# IO.net
KiCad netlist of a schematic drawn in Altium Designer
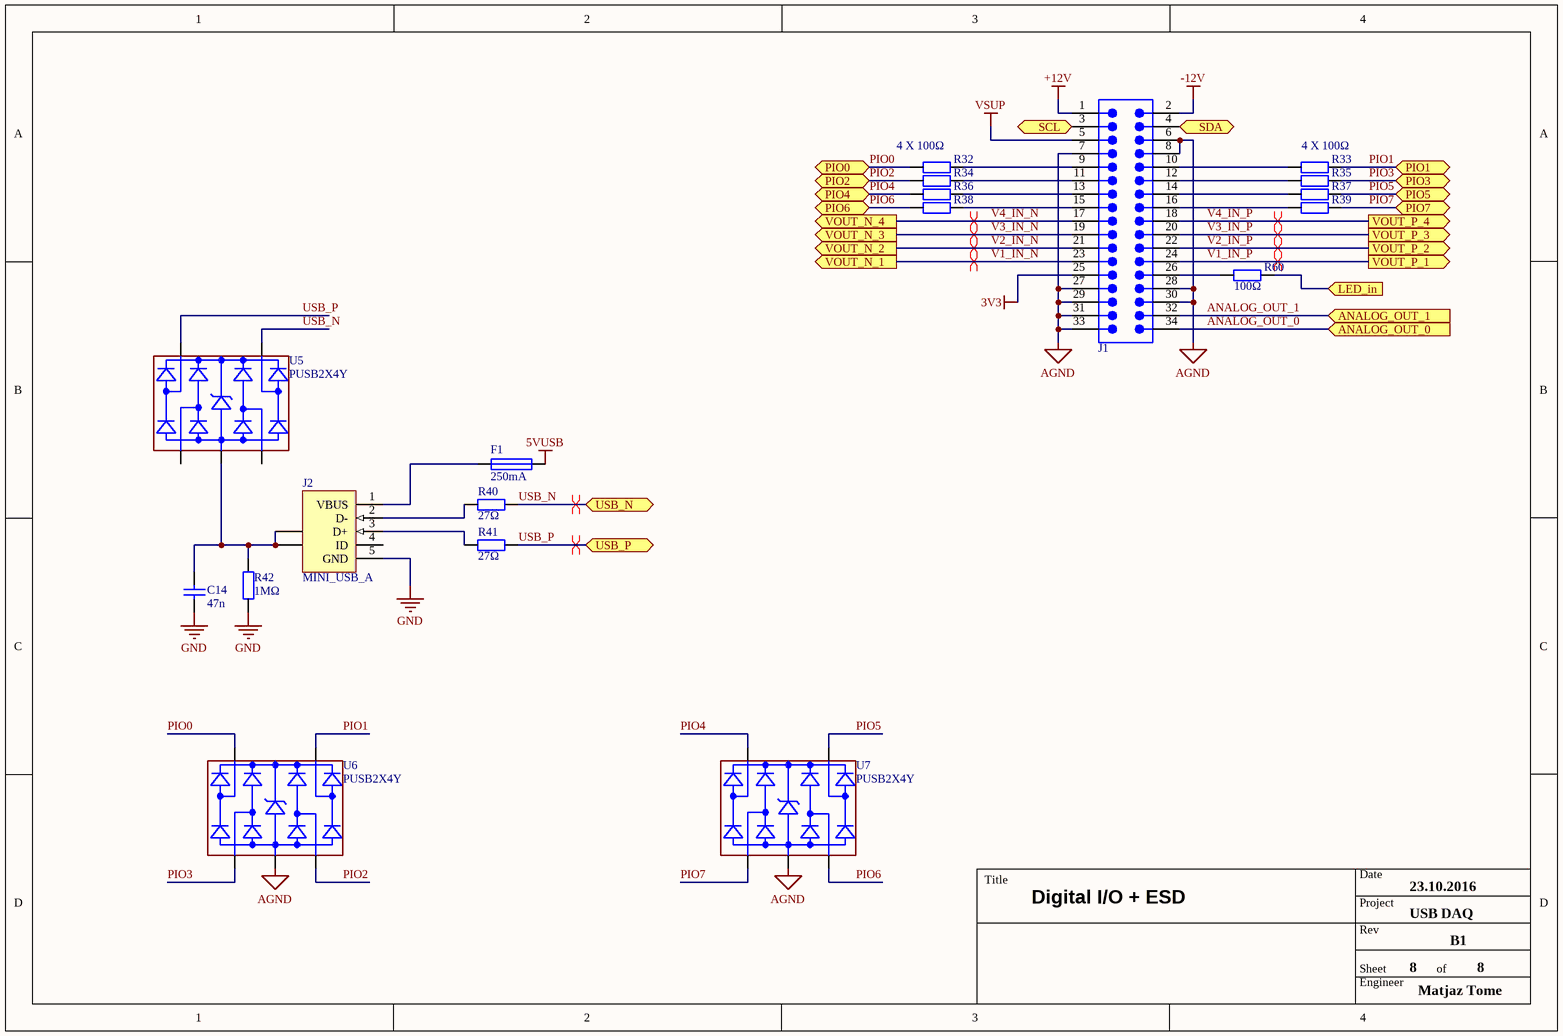
[diagram p0: IO.SchDoc]

(export (version "E")
  (design (tool "Eeschema 10.0.6"))
  (components
    (comp (ref "C14")
      (value "47n")
      (footprint "0603C")
      (description "ceramic X7R SMD capacitor smd 0603 47nF 16V")
      (fields (field (name "PART NUMBER") "RSC0007") (field (name "MANUFACTURER") "Multicomp"))
      (libsource (lib "components") (part "Capacitor"))
    )
    (comp (ref "F1")
      (value "250mA")
      (footprint "1206")
      (description "Polyfuse 250 mA holding current, 500 mA trip current")
      (fields (field (name "PART NUMBER") "XXF0001") (field (name "MANUFACTURER") "Littelfuse"))
      (libsource (lib "components") (part "Fuse"))
    )
    (comp (ref "J1")
      (value "IDC34R")
      (footprint "IDC34R")
      (description "Harting IDC connector 2X17")
      (fields (field (name "PART NUMBER") "CHI0002") (field (name "MANUFACTURER") "Harting"))
      (libsource (lib "components") (part "IDC34R"))
    )
    (comp (ref "J2")
      (value "MINI_USB_A")
      (footprint "MICRO_USB_A")
      (description "CONNECTOR, MICRO USB B, SMD, 5WAY")
      (fields (field (name "PART NUMBER") "XCU0003") (field (name "MANUFACTURER") "FCI"))
      (libsource (lib "components") (part "MINI_USB_A"))
    )
    (comp (ref "R32")
      (value "100Ω")
      (footprint "0603R")
      (description "resistor smd 0603 100Ω 5% 0.1w")
      (fields (field (name "PART NUMBER") "XRS0016") (field (name "MANUFACTURER") "Multicomp"))
      (libsource (lib "components") (part "Resistor"))
    )
    (comp (ref "R33")
      (value "100Ω")
      (footprint "0603R")
      (description "resistor smd 0603 100Ω 5% 0.1w")
      (fields (field (name "PART NUMBER") "XRS0016") (field (name "MANUFACTURER") "Multicomp"))
      (libsource (lib "components") (part "Resistor"))
    )
    (comp (ref "R34")
      (value "100Ω")
      (footprint "0603R")
      (description "resistor smd 0603 100Ω 5% 0.1w")
      (fields (field (name "PART NUMBER") "XRS0016") (field (name "MANUFACTURER") "Multicomp"))
      (libsource (lib "components") (part "Resistor"))
    )
    (comp (ref "R35")
      (value "100Ω")
      (footprint "0603R")
      (description "resistor smd 0603 100Ω 5% 0.1w")
      (fields (field (name "PART NUMBER") "XRS0016") (field (name "MANUFACTURER") "Multicomp"))
      (libsource (lib "components") (part "Resistor"))
    )
    (comp (ref "R36")
      (value "100Ω")
      (footprint "0603R")
      (description "resistor smd 0603 100Ω 5% 0.1w")
      (fields (field (name "PART NUMBER") "XRS0016") (field (name "MANUFACTURER") "Multicomp"))
      (libsource (lib "components") (part "Resistor"))
    )
    (comp (ref "R37")
      (value "100Ω")
      (footprint "0603R")
      (description "resistor smd 0603 100Ω 5% 0.1w")
      (fields (field (name "PART NUMBER") "XRS0016") (field (name "MANUFACTURER") "Multicomp"))
      (libsource (lib "components") (part "Resistor"))
    )
    (comp (ref "R38")
      (value "100Ω")
      (footprint "0603R")
      (description "resistor smd 0603 100Ω 5% 0.1w")
      (fields (field (name "PART NUMBER") "XRS0016") (field (name "MANUFACTURER") "Multicomp"))
      (libsource (lib "components") (part "Resistor"))
    )
    (comp (ref "R39")
      (value "100Ω")
      (footprint "0603R")
      (description "resistor smd 0603 100Ω 5% 0.1w")
      (fields (field (name "PART NUMBER") "XRS0016") (field (name "MANUFACTURER") "Multicomp"))
      (libsource (lib "components") (part "Resistor"))
    )
    (comp (ref "R40")
      (value "27Ω")
      (footprint "0603R")
      (description "resistor smd 0603 27Ω 5% 0.1w")
      (fields (field (name "PART NUMBER") "XRS0033") (field (name "MANUFACTURER") "Panasonic"))
      (libsource (lib "components") (part "Resistor"))
    )
    (comp (ref "R41")
      (value "27Ω")
      (footprint "0603R")
      (description "resistor smd 0603 27Ω 5% 0.1w")
      (fields (field (name "PART NUMBER") "XRS0033") (field (name "MANUFACTURER") "Panasonic"))
      (libsource (lib "components") (part "Resistor"))
    )
    (comp (ref "R42")
      (value "1MΩ")
      (footprint "0603R")
      (description "resistor smd 0603 1MΩ 5% 0.1w")
      (fields (field (name "PART NUMBER") "XRS0035") (field (name "MANUFACTURER") "Multicomp"))
      (libsource (lib "") (part "Resistor_1"))
    )
    (comp (ref "R60")
      (value "100Ω")
      (footprint "0603R")
      (description "resistor smd 0603 100Ω 5% 0.1w")
      (fields (field (name "PART NUMBER") "XRS0016") (field (name "MANUFACTURER") "Multicomp"))
      (libsource (lib "components") (part "Resistor"))
    )
    (comp (ref "U5")
      (value "PUSB2X4Y")
      (footprint "SOT363")
      (description "ESD protection for high-speed interfaces")
      (fields (field (name "PART NUMBER") "XDE0000") (field (name "MANUFACTURER") "Multicomp"))
      (libsource (lib "components") (part "ESD2_4CH"))
    )
    (comp (ref "U6")
      (value "PUSB2X4Y")
      (footprint "SOT363")
      (description "ESD protection for high-speed interfaces")
      (fields (field (name "PART NUMBER") "XDE0000") (field (name "MANUFACTURER") "Multicomp"))
      (libsource (lib "components") (part "ESD2_4CH"))
    )
    (comp (ref "U7")
      (value "PUSB2X4Y")
      (footprint "SOT363")
      (description "ESD protection for high-speed interfaces")
      (fields (field (name "PART NUMBER") "XDE0000") (field (name "MANUFACTURER") "Multicomp"))
      (libsource (lib "components") (part "ESD2_4CH"))
    )
  )
  (nets
    (net (code "1") (name "+12V") (class "Default")
      (node (ref "J1") (pin "1") (pinfunction "1_1") (pintype "passive"))
    )
    (net (code "2") (name "-12V") (class "Default")
      (node (ref "J1") (pin "2") (pinfunction "2_2") (pintype "passive"))
    )
    (net (code "3") (name "/ANALOG_OUT_0") (class "Default")
      (node (ref "J1") (pin "34") (pinfunction "34_34") (pintype "passive"))
    )
    (net (code "4") (name "/ANALOG_OUT_1") (class "Default")
      (node (ref "J1") (pin "32") (pinfunction "32_32") (pintype "passive"))
    )
    (net (code "5") (name "/LED_in") (class "Default")
      (node (ref "R60") (pin "2") (pinfunction "2_2") (pintype "passive"))
    )
    (net (code "6") (name "/PIO0") (class "Default")
      (node (ref "R32") (pin "1") (pinfunction "1_1") (pintype "passive"))
      (node (ref "U6") (pin "6") (pinfunction "6_6") (pintype "passive"))
    )
    (net (code "7") (name "/PIO1") (class "Default")
      (node (ref "R33") (pin "2") (pinfunction "2_2") (pintype "passive"))
      (node (ref "U6") (pin "4") (pinfunction "4_4") (pintype "passive"))
    )
    (net (code "8") (name "/PIO2") (class "Default")
      (node (ref "R34") (pin "1") (pinfunction "1_1") (pintype "passive"))
      (node (ref "U6") (pin "3") (pinfunction "3_3") (pintype "passive"))
    )
    (net (code "9") (name "/PIO3") (class "Default")
      (node (ref "R35") (pin "2") (pinfunction "2_2") (pintype "passive"))
      (node (ref "U6") (pin "1") (pinfunction "1_1") (pintype "passive"))
    )
    (net (code "10") (name "/PIO4") (class "Default")
      (node (ref "R36") (pin "1") (pinfunction "1_1") (pintype "passive"))
      (node (ref "U7") (pin "6") (pinfunction "6_6") (pintype "passive"))
    )
    (net (code "11") (name "/PIO5") (class "Default")
      (node (ref "R37") (pin "2") (pinfunction "2_2") (pintype "passive"))
      (node (ref "U7") (pin "4") (pinfunction "4_4") (pintype "passive"))
    )
    (net (code "12") (name "/PIO6") (class "Default")
      (node (ref "R38") (pin "1") (pinfunction "1_1") (pintype "passive"))
      (node (ref "U7") (pin "3") (pinfunction "3_3") (pintype "passive"))
    )
    (net (code "13") (name "/PIO7") (class "Default")
      (node (ref "R39") (pin "2") (pinfunction "2_2") (pintype "passive"))
      (node (ref "U7") (pin "1") (pinfunction "1_1") (pintype "passive"))
    )
    (net (code "14") (name "/SCL") (class "Default")
      (node (ref "J1") (pin "3") (pinfunction "3_3") (pintype "passive"))
    )
    (net (code "15") (name "/SDA") (class "Default")
      (node (ref "J1") (pin "4") (pinfunction "4_4") (pintype "passive"))
    )
    (net (code "16") (name "/USB_N") (class "Default")
      (node (ref "R40") (pin "2") (pinfunction "2_2") (pintype "passive"))
      (node (ref "U5") (pin "4") (pinfunction "4_4") (pintype "passive"))
    )
    (net (code "17") (name "/USB_P") (class "Default")
      (node (ref "R41") (pin "2") (pinfunction "2_2") (pintype "passive"))
      (node (ref "U5") (pin "6") (pinfunction "6_6") (pintype "passive"))
    )
    (net (code "18") (name "/V1_IN_N") (class "Default")
      (node (ref "J1") (pin "23") (pinfunction "23_23") (pintype "passive"))
    )
    (net (code "19") (name "/V1_IN_P") (class "Default")
      (node (ref "J1") (pin "24") (pinfunction "24_24") (pintype "passive"))
    )
    (net (code "20") (name "/V2_IN_N") (class "Default")
      (node (ref "J1") (pin "21") (pinfunction "21_21") (pintype "passive"))
    )
    (net (code "21") (name "/V2_IN_P") (class "Default")
      (node (ref "J1") (pin "22") (pinfunction "22_22") (pintype "passive"))
    )
    (net (code "22") (name "/V3_IN_N") (class "Default")
      (node (ref "J1") (pin "19") (pinfunction "19_19") (pintype "passive"))
    )
    (net (code "23") (name "/V3_IN_P") (class "Default")
      (node (ref "J1") (pin "20") (pinfunction "20_20") (pintype "passive"))
    )
    (net (code "24") (name "/V4_IN_N") (class "Default")
      (node (ref "J1") (pin "17") (pinfunction "17_17") (pintype "passive"))
    )
    (net (code "25") (name "/V4_IN_P") (class "Default")
      (node (ref "J1") (pin "18") (pinfunction "18_18") (pintype "passive"))
    )
    (net (code "26") (name "3V3") (class "Default")
      (node (ref "J1") (pin "25") (pinfunction "25_25") (pintype "passive"))
    )
    (net (code "27") (name "5VUSB") (class "Default")
      (node (ref "F1") (pin "2") (pinfunction "2_2") (pintype "passive"))
    )
    (net (code "28") (name "AGND") (class "Default")
      (node (ref "J1") (pin "27") (pinfunction "27_27") (pintype "passive"))
      (node (ref "J1") (pin "28") (pinfunction "28_28") (pintype "passive"))
      (node (ref "J1") (pin "29") (pinfunction "29_29") (pintype "passive"))
      (node (ref "J1") (pin "30") (pinfunction "30_30") (pintype "passive"))
      (node (ref "J1") (pin "31") (pinfunction "31_31") (pintype "passive"))
      (node (ref "J1") (pin "33") (pinfunction "33_33") (pintype "passive"))
      (node (ref "J1") (pin "6") (pinfunction "6_6") (pintype "passive"))
      (node (ref "J1") (pin "7") (pinfunction "7_7") (pintype "passive"))
      (node (ref "J1") (pin "8") (pinfunction "8_8") (pintype "passive"))
      (node (ref "U6") (pin "2") (pinfunction "2_2") (pintype "passive"))
      (node (ref "U7") (pin "2") (pinfunction "2_2") (pintype "passive"))
    )
    (net (code "29") (name "GND") (class "Default")
      (node (ref "C14") (pin "1") (pinfunction "1_1") (pintype "passive"))
      (node (ref "J2") (pin "5") (pinfunction "GND_5") (pintype "power_in"))
      (node (ref "R42") (pin "1") (pinfunction "1_1") (pintype "passive"))
    )
    (net (code "30") (name "Net-(C14-Pad2)") (class "Default")
      (node (ref "C14") (pin "2") (pinfunction "2_2") (pintype "passive"))
      (node (ref "J2") (pin "6") (pinfunction "SHLD_6") (pintype "passive"))
      (node (ref "J2") (pin "7") (pinfunction "SHLD_7") (pintype "passive"))
      (node (ref "R42") (pin "2") (pinfunction "2_2") (pintype "passive"))
      (node (ref "U5") (pin "2") (pinfunction "2_2") (pintype "passive"))
    )
    (net (code "31") (name "Net-(J1-Pad9)") (class "Default")
      (node (ref "J1") (pin "9") (pinfunction "9_9") (pintype "passive"))
      (node (ref "R32") (pin "2") (pinfunction "2_2") (pintype "passive"))
    )
    (net (code "32") (name "Net-(J1-Pad10)") (class "Default")
      (node (ref "J1") (pin "10") (pinfunction "10_10") (pintype "passive"))
      (node (ref "R33") (pin "1") (pinfunction "1_1") (pintype "passive"))
    )
    (net (code "33") (name "Net-(J1-Pad11)") (class "Default")
      (node (ref "J1") (pin "11") (pinfunction "11_11") (pintype "passive"))
      (node (ref "R34") (pin "2") (pinfunction "2_2") (pintype "passive"))
    )
    (net (code "34") (name "Net-(J1-Pad12)") (class "Default")
      (node (ref "J1") (pin "12") (pinfunction "12_12") (pintype "passive"))
      (node (ref "R35") (pin "1") (pinfunction "1_1") (pintype "passive"))
    )
    (net (code "35") (name "Net-(J1-Pad13)") (class "Default")
      (node (ref "J1") (pin "13") (pinfunction "13_13") (pintype "passive"))
      (node (ref "R36") (pin "2") (pinfunction "2_2") (pintype "passive"))
    )
    (net (code "36") (name "Net-(J1-Pad14)") (class "Default")
      (node (ref "J1") (pin "14") (pinfunction "14_14") (pintype "passive"))
      (node (ref "R37") (pin "1") (pinfunction "1_1") (pintype "passive"))
    )
    (net (code "37") (name "Net-(J1-Pad15)") (class "Default")
      (node (ref "J1") (pin "15") (pinfunction "15_15") (pintype "passive"))
      (node (ref "R38") (pin "2") (pinfunction "2_2") (pintype "passive"))
    )
    (net (code "38") (name "Net-(J1-Pad16)") (class "Default")
      (node (ref "J1") (pin "16") (pinfunction "16_16") (pintype "passive"))
      (node (ref "R39") (pin "1") (pinfunction "1_1") (pintype "passive"))
    )
    (net (code "39") (name "Net-(J1-Pad26)") (class "Default")
      (node (ref "J1") (pin "26") (pinfunction "26_26") (pintype "passive"))
      (node (ref "R60") (pin "1") (pinfunction "1_1") (pintype "passive"))
    )
    (net (code "40") (name "Net-(J2-D+)") (class "Default")
      (node (ref "J2") (pin "3") (pinfunction "D+_3") (pintype "input"))
      (node (ref "R41") (pin "1") (pinfunction "1_1") (pintype "passive"))
    )
    (net (code "41") (name "Net-(J2-D-)") (class "Default")
      (node (ref "J2") (pin "2") (pinfunction "D-_2") (pintype "input"))
      (node (ref "R40") (pin "1") (pinfunction "1_1") (pintype "passive"))
    )
    (net (code "42") (name "Net-(J2-VBUS)") (class "Default")
      (node (ref "F1") (pin "1") (pinfunction "1_1") (pintype "passive"))
      (node (ref "J2") (pin "1") (pinfunction "VBUS_1") (pintype "power_in"))
    )
    (net (code "43") (name "VSUP") (class "Default")
      (node (ref "J1") (pin "5") (pinfunction "5_5") (pintype "passive"))
    )
    (net (code "44") (name "unconnected-(J2-ID-Pad4)") (class "Default")
      (node (ref "J2") (pin "4") (pinfunction "ID_4") (pintype "passive"))
    )
    (net (code "45") (name "unconnected-(U5-Pad1)") (class "Default")
      (node (ref "U5") (pin "1") (pinfunction "1_1") (pintype "passive"))
    )
    (net (code "46") (name "unconnected-(U5-Pad3)") (class "Default")
      (node (ref "U5") (pin "3") (pinfunction "3_3") (pintype "passive"))
    )
  )
)
